# TivaC.net
KiCad netlist of a schematic drawn in Altium Designer
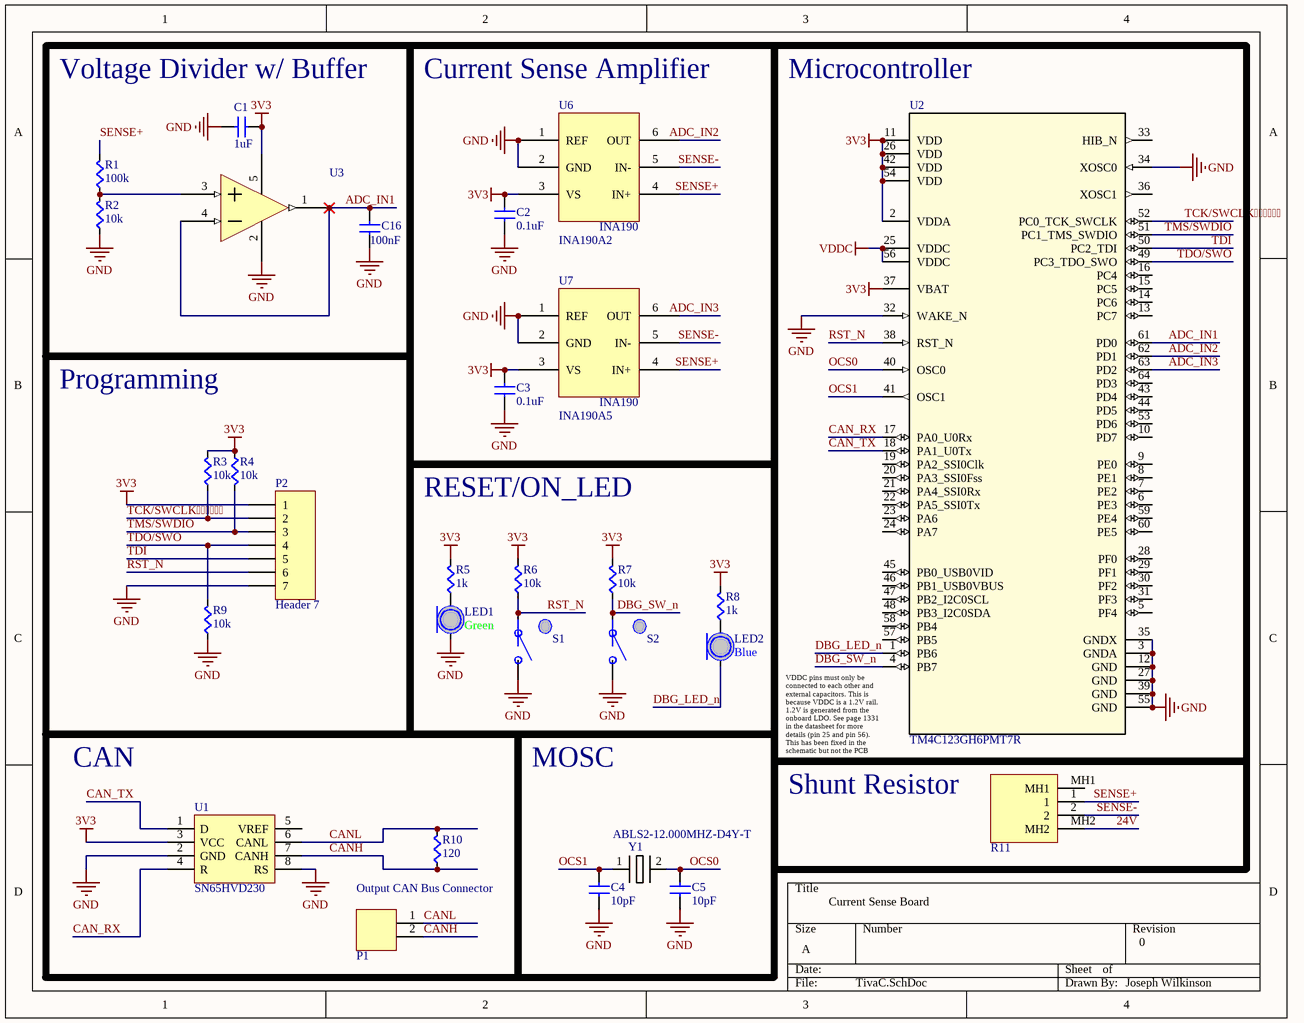
[diagram p0: TivaC.SchDoc]

(export (version "E")
  (design (tool "Eeschema 10.0.6"))
  (components
    (comp (ref "C1")
      (value "1uF")
      (footprint "CAPC0603")
      (fields (field (name "Comment") "Cap"))
      (libsource (lib "Passives") (part "Cap"))
    )
    (comp (ref "C2")
      (value "0.1uF")
      (footprint "CAPC0603")
      (fields (field (name "Comment") "Cap"))
      (libsource (lib "Passives") (part "Cap"))
    )
    (comp (ref "C3")
      (value "0.1uF")
      (footprint "CAPC0603")
      (fields (field (name "Comment") "Cap"))
      (libsource (lib "Passives") (part "Cap"))
    )
    (comp (ref "C4")
      (value "10pF")
      (footprint "CAPC0603")
      (fields (field (name "Comment") "Cap"))
      (libsource (lib "Passives") (part "Cap"))
    )
    (comp (ref "C5")
      (value "10pF")
      (footprint "CAPC0603")
      (fields (field (name "Comment") "Cap"))
      (libsource (lib "Passives") (part "Cap"))
    )
    (comp (ref "C16")
      (value "100nF")
      (footprint "CAPC0603")
      (fields (field (name "Comment") "Cap"))
      (libsource (lib "Passives") (part "Cap"))
    )
    (comp (ref "LED1")
      (value "LED")
      (footprint "LED0603")
      (fields (field (name "COLOR") "Green"))
      (libsource (lib "Semiconductors") (part "LED"))
    )
    (comp (ref "LED2")
      (value "LED")
      (footprint "LED0603")
      (fields (field (name "COLOR") "Blue"))
      (libsource (lib "Semiconductors") (part "LED"))
    )
    (comp (ref "P1")
      (value "2-pin Vert Sherlock")
      (footprint "MOLEX-HDR-1X2-SHERLOCK-VERT")
      (libsource (lib "Connectors") (part "MOLEX-HDR-1x2-SHERLOCK_VERT"))
    )
    (comp (ref "P2")
      (value "Header 7")
      (footprint "HDR1X7")
      (description "Header, 7-Pin")
      (fields (field (name "PUBLISHER") "Altium Limited"))
      (libsource (lib "Miscellaneous Connectors") (part "Header 7"))
    )
    (comp (ref "R1")
      (value "100k")
      (footprint "RES0603")
      (fields (field (name "Comment") "Res"))
      (libsource (lib "Passives") (part "Res"))
    )
    (comp (ref "R2")
      (value "10k")
      (footprint "RES0603")
      (fields (field (name "Comment") "Res"))
      (libsource (lib "Passives") (part "Res"))
    )
    (comp (ref "R3")
      (value "10k")
      (footprint "RES0603")
      (fields (field (name "Comment") "Res"))
      (libsource (lib "Passives") (part "Res"))
    )
    (comp (ref "R4")
      (value "10k")
      (footprint "RES0603")
      (fields (field (name "Comment") "Res"))
      (libsource (lib "Passives") (part "Res"))
    )
    (comp (ref "R5")
      (value "1k")
      (footprint "RES0603")
      (fields (field (name "Comment") "Res"))
      (libsource (lib "Passives") (part "Res"))
    )
    (comp (ref "R6")
      (value "10k")
      (footprint "RES0603")
      (fields (field (name "Comment") "Res"))
      (libsource (lib "Passives") (part "Res"))
    )
    (comp (ref "R7")
      (value "10k")
      (footprint "RES0603")
      (fields (field (name "Comment") "Res"))
      (libsource (lib "Passives") (part "Res"))
    )
    (comp (ref "R8")
      (value "1k")
      (footprint "RES0603")
      (fields (field (name "Comment") "Res"))
      (libsource (lib "Passives") (part "Res"))
    )
    (comp (ref "R9")
      (value "10k")
      (footprint "RES0603")
      (fields (field (name "Comment") "Res"))
      (libsource (lib "Passives") (part "Res"))
    )
    (comp (ref "R10")
      (value "120")
      (footprint "RES0603")
      (fields (field (name "Comment") "Res"))
      (libsource (lib "Passives") (part "Res"))
    )
    (comp (ref "R11")
      (value "SH6918F500BPEP")
      (footprint "SH6918F500BPEP")
      (description "Copper bus bar with shunt resistor integrated")
      (fields (field (name "MOUSER PART NUMBER") "588-SH6918F500BPEP"))
      (libsource (lib "Passives") (part "SH6918F500BPEP"))
    )
    (comp (ref "S1")
      (value "Button")
      (footprint "PTS645xxxxSMTR92")
      (description "SPST Button")
      (libsource (lib "Passives") (part "Button"))
    )
    (comp (ref "S2")
      (value "Button")
      (footprint "PTS645xxxxSMTR92")
      (description "SPST Button")
      (libsource (lib "Passives") (part "Button"))
    )
    (comp (ref "U1")
      (value "SN65HVD230")
      (footprint "SOIC-8pin")
      (description "3.3V CAN Bus Transceiver")
      (libsource (lib "ICs") (part "SN65HVD230"))
    )
    (comp (ref "U2")
      (value "TM4C123GH6PMT7R")
      (footprint "TM4C123GH6PMT7R_L")
      (description "Imported")
      (fields
        (field (name "PARTNUMBER") "TM4C123GH6PMTR")
        (field (name "ALTERNATE_PARTNUMBER") "TM4C123GH6PMT")
      )
      (libsource (lib "ICs") (part "TM4C123GH6PMT7R"))
    )
    (comp (ref "U3")
      (value "MCP6L01")
      (footprint "MCP6L01R")
      (description "Op Amp Rail-to-Rail 1Mhz")
      (libsource (lib "ICs") (part "MCP6L01"))
    )
    (comp (ref "U6")
      (value "INA190A2")
      (footprint "SC70 (DCK)")
      (libsource (lib "projectLib") (part "INA190"))
    )
    (comp (ref "U7")
      (value "INA190A5")
      (footprint "SC70 (DCK)")
      (libsource (lib "projectLib") (part "INA190"))
    )
    (comp (ref "Y1")
      (value "ABLS2-12.000MHZ-D4Y-T")
      (footprint "HC49/US")
      (description "12MHz ±30ppm Crystal 18pF 50 Ohm -40°C ~ 85°C Surface Mount HC49/US")
      (libsource (lib "ICs") (part "ABLS2-12.000MHZ-D4Y-T"))
    )
  )
  (nets
    (net (code "1") (name "/24V") (class "Default")
      (node (ref "R11") (pin "MH2") (pinfunction "MH2_MH2") (pintype "passive"))
    )
    (net (code "2") (name "/ADC_IN1") (class "Default")
      (node (ref "C16") (pin "1") (pinfunction "A_1") (pintype "passive"))
      (node (ref "U2") (pin "61") (pinfunction "PD0_61") (pintype "bidirectional"))
      (node (ref "U3") (pin "1") (pinfunction "VOUT_1") (pintype "output"))
      (node (ref "U3") (pin "4") (pinfunction "VIN-_4") (pintype "input"))
    )
    (net (code "3") (name "/ADC_IN2") (class "Default")
      (node (ref "U2") (pin "62") (pinfunction "PD1_62") (pintype "bidirectional"))
      (node (ref "U6") (pin "6") (pinfunction "OUT_6") (pintype "passive"))
    )
    (net (code "4") (name "/ADC_IN3") (class "Default")
      (node (ref "U2") (pin "63") (pinfunction "PD2_63") (pintype "bidirectional"))
      (node (ref "U7") (pin "6") (pinfunction "OUT_6") (pintype "passive"))
    )
    (net (code "5") (name "/CANH") (class "Default")
      (node (ref "P1") (pin "2") (pinfunction "2_2") (pintype "passive"))
      (node (ref "R10") (pin "2") (pinfunction "B_2") (pintype "passive"))
      (node (ref "U1") (pin "7") (pinfunction "CANH_7") (pintype "passive"))
    )
    (net (code "6") (name "/CANL") (class "Default")
      (node (ref "P1") (pin "1") (pinfunction "1_1") (pintype "passive"))
      (node (ref "R10") (pin "1") (pinfunction "A_1") (pintype "passive"))
      (node (ref "U1") (pin "6") (pinfunction "CANL_6") (pintype "passive"))
    )
    (net (code "7") (name "/CAN_RX") (class "Default")
      (node (ref "U1") (pin "4") (pinfunction "R_4") (pintype "passive"))
      (node (ref "U2") (pin "17") (pinfunction "PA0_U0Rx_17") (pintype "bidirectional"))
    )
    (net (code "8") (name "/CAN_TX") (class "Default")
      (node (ref "U1") (pin "1") (pinfunction "D_1") (pintype "passive"))
      (node (ref "U2") (pin "18") (pinfunction "PA1_U0Tx_18") (pintype "bidirectional"))
    )
    (net (code "9") (name "/DBG_LED_n") (class "Default")
      (node (ref "LED2") (pin "C") (pinfunction "C_C") (pintype "passive"))
      (node (ref "U2") (pin "1") (pinfunction "PB6_1") (pintype "bidirectional"))
    )
    (net (code "10") (name "/DBG_SW_n") (class "Default")
      (node (ref "R7") (pin "2") (pinfunction "B_2") (pintype "passive"))
      (node (ref "S2") (pin "A") (pinfunction "A_A") (pintype "passive"))
      (node (ref "U2") (pin "4") (pinfunction "PB7_4") (pintype "bidirectional"))
    )
    (net (code "11") (name "/OCS0") (class "Default")
      (node (ref "C5") (pin "1") (pinfunction "A_1") (pintype "passive"))
      (node (ref "U2") (pin "40") (pinfunction "OSC0_40") (pintype "input"))
      (node (ref "Y1") (pin "2") (pinfunction "2_2") (pintype "passive"))
    )
    (net (code "12") (name "/OCS1") (class "Default")
      (node (ref "C4") (pin "1") (pinfunction "A_1") (pintype "passive"))
      (node (ref "U2") (pin "41") (pinfunction "OSC1_41") (pintype "output"))
      (node (ref "Y1") (pin "1") (pinfunction "1_1") (pintype "passive"))
    )
    (net (code "13") (name "/RST_N") (class "Default")
      (node (ref "P2") (pin "6") (pinfunction "6_6") (pintype "passive"))
      (node (ref "R6") (pin "2") (pinfunction "B_2") (pintype "passive"))
      (node (ref "S1") (pin "A") (pinfunction "A_A") (pintype "passive"))
      (node (ref "U2") (pin "38") (pinfunction "RST_N_38") (pintype "input"))
    )
    (net (code "14") (name "/SENSE+") (class "Default")
      (node (ref "R1") (pin "1") (pinfunction "A_1") (pintype "passive"))
      (node (ref "R11") (pin "1") (pinfunction "1_1") (pintype "passive"))
      (node (ref "U6") (pin "4") (pinfunction "IN+_4") (pintype "passive"))
      (node (ref "U7") (pin "4") (pinfunction "IN+_4") (pintype "passive"))
    )
    (net (code "15") (name "/SENSE-") (class "Default")
      (node (ref "R11") (pin "2") (pinfunction "2_2") (pintype "passive"))
      (node (ref "U6") (pin "5") (pinfunction "IN-_5") (pintype "passive"))
      (node (ref "U7") (pin "5") (pinfunction "IN-_5") (pintype "passive"))
    )
    (net (code "16") (name "/TCK{slash}SWCLK") (class "Default")
      (node (ref "P2") (pin "2") (pinfunction "2_2") (pintype "passive"))
      (node (ref "R3") (pin "2") (pinfunction "B_2") (pintype "passive"))
      (node (ref "U2") (pin "52") (pinfunction "PC0_TCK_SWCLK_52") (pintype "bidirectional"))
    )
    (net (code "17") (name "/TDI") (class "Default")
      (node (ref "P2") (pin "5") (pinfunction "5_5") (pintype "passive"))
      (node (ref "U2") (pin "50") (pinfunction "PC2_TDI_50") (pintype "bidirectional"))
    )
    (net (code "18") (name "/TDO{slash}SWO") (class "Default")
      (node (ref "P2") (pin "4") (pinfunction "4_4") (pintype "passive"))
      (node (ref "R9") (pin "1") (pinfunction "A_1") (pintype "passive"))
      (node (ref "U2") (pin "49") (pinfunction "PC3_TDO_SWO_49") (pintype "bidirectional"))
    )
    (net (code "19") (name "/TMS{slash}SWDIO") (class "Default")
      (node (ref "P2") (pin "3") (pinfunction "3_3") (pintype "passive"))
      (node (ref "R4") (pin "1") (pinfunction "A_1") (pintype "passive"))
      (node (ref "U2") (pin "51") (pinfunction "PC1_TMS_SWDIO_51") (pintype "bidirectional"))
    )
    (net (code "20") (name "3V3") (class "Default")
      (node (ref "C1") (pin "2") (pinfunction "B_2") (pintype "passive"))
      (node (ref "C2") (pin "1") (pinfunction "A_1") (pintype "passive"))
      (node (ref "C3") (pin "1") (pinfunction "A_1") (pintype "passive"))
      (node (ref "P2") (pin "1") (pinfunction "1_1") (pintype "passive"))
      (node (ref "R3") (pin "1") (pinfunction "A_1") (pintype "passive"))
      (node (ref "R4") (pin "2") (pinfunction "B_2") (pintype "passive"))
      (node (ref "R5") (pin "1") (pinfunction "A_1") (pintype "passive"))
      (node (ref "R6") (pin "1") (pinfunction "A_1") (pintype "passive"))
      (node (ref "R7") (pin "1") (pinfunction "A_1") (pintype "passive"))
      (node (ref "R8") (pin "1") (pinfunction "A_1") (pintype "passive"))
      (node (ref "U1") (pin "3") (pinfunction "VCC_3") (pintype "passive"))
      (node (ref "U2") (pin "11") (pinfunction "VDD_11") (pintype "power_in"))
      (node (ref "U2") (pin "2") (pinfunction "VDDA_2") (pintype "power_in"))
      (node (ref "U2") (pin "26") (pinfunction "VDD_26") (pintype "power_in"))
      (node (ref "U2") (pin "37") (pinfunction "VBAT_37") (pintype "power_in"))
      (node (ref "U2") (pin "42") (pinfunction "VDD_42") (pintype "power_in"))
      (node (ref "U2") (pin "54") (pinfunction "VDD_54") (pintype "power_in"))
      (node (ref "U3") (pin "5") (pinfunction "VDD_5") (pintype "power_in"))
      (node (ref "U6") (pin "3") (pinfunction "VS_3") (pintype "passive"))
      (node (ref "U7") (pin "3") (pinfunction "VS_3") (pintype "passive"))
    )
    (net (code "21") (name "GND") (class "Default")
      (node (ref "C1") (pin "1") (pinfunction "A_1") (pintype "passive"))
      (node (ref "C16") (pin "2") (pinfunction "B_2") (pintype "passive"))
      (node (ref "C2") (pin "2") (pinfunction "B_2") (pintype "passive"))
      (node (ref "C3") (pin "2") (pinfunction "B_2") (pintype "passive"))
      (node (ref "C4") (pin "2") (pinfunction "B_2") (pintype "passive"))
      (node (ref "C5") (pin "2") (pinfunction "B_2") (pintype "passive"))
      (node (ref "LED1") (pin "C") (pinfunction "C_C") (pintype "passive"))
      (node (ref "P2") (pin "7") (pinfunction "7_7") (pintype "passive"))
      (node (ref "R2") (pin "2") (pinfunction "B_2") (pintype "passive"))
      (node (ref "R9") (pin "2") (pinfunction "B_2") (pintype "passive"))
      (node (ref "S1") (pin "B") (pinfunction "B_B") (pintype "passive"))
      (node (ref "S2") (pin "B") (pinfunction "B_B") (pintype "passive"))
      (node (ref "U1") (pin "2") (pinfunction "GND_2") (pintype "passive"))
      (node (ref "U1") (pin "8") (pinfunction "RS_8") (pintype "passive"))
      (node (ref "U2") (pin "12") (pinfunction "GND_12") (pintype "power_in"))
      (node (ref "U2") (pin "27") (pinfunction "GND_27") (pintype "power_in"))
      (node (ref "U2") (pin "3") (pinfunction "GNDA_3") (pintype "power_in"))
      (node (ref "U2") (pin "32") (pinfunction "WAKE_N_32") (pintype "input"))
      (node (ref "U2") (pin "34") (pinfunction "XOSC0_34") (pintype "input"))
      (node (ref "U2") (pin "35") (pinfunction "GNDX_35") (pintype "power_in"))
      (node (ref "U2") (pin "39") (pinfunction "GND_39") (pintype "power_in"))
      (node (ref "U2") (pin "55") (pinfunction "GND_55") (pintype "power_in"))
      (node (ref "U3") (pin "2") (pinfunction "VSS_2") (pintype "power_in"))
      (node (ref "U6") (pin "1") (pinfunction "REF_1") (pintype "passive"))
      (node (ref "U6") (pin "2") (pinfunction "GND_2") (pintype "passive"))
      (node (ref "U7") (pin "1") (pinfunction "REF_1") (pintype "passive"))
      (node (ref "U7") (pin "2") (pinfunction "GND_2") (pintype "passive"))
    )
    (net (code "22") (name "Net-(R1-B)") (class "Default")
      (node (ref "R1") (pin "2") (pinfunction "B_2") (pintype "passive"))
      (node (ref "R2") (pin "1") (pinfunction "A_1") (pintype "passive"))
      (node (ref "U3") (pin "3") (pinfunction "VIN+_3") (pintype "input"))
    )
    (net (code "23") (name "Net-(R5-B)") (class "Default")
      (node (ref "LED1") (pin "A") (pinfunction "A_A") (pintype "passive"))
      (node (ref "R5") (pin "2") (pinfunction "B_2") (pintype "passive"))
    )
    (net (code "24") (name "Net-(R8-B)") (class "Default")
      (node (ref "LED2") (pin "A") (pinfunction "A_A") (pintype "passive"))
      (node (ref "R8") (pin "2") (pinfunction "B_2") (pintype "passive"))
    )
    (net (code "25") (name "VDDC") (class "Default")
      (node (ref "U2") (pin "25") (pinfunction "VDDC_25") (pintype "power_in"))
      (node (ref "U2") (pin "56") (pinfunction "VDDC_56") (pintype "power_in"))
    )
    (net (code "26") (name "unconnected-(R11-PadMH1)") (class "Default")
      (node (ref "R11") (pin "MH1") (pinfunction "MH1_MH1") (pintype "passive"))
    )
    (net (code "27") (name "unconnected-(U1-VREF-Pad5)") (class "Default")
      (node (ref "U1") (pin "5") (pinfunction "VREF_5") (pintype "passive"))
    )
    (net (code "28") (name "unconnected-(U2-HIB_N-Pad33)") (class "Default")
      (node (ref "U2") (pin "33") (pinfunction "HIB_N_33") (pintype "output"))
    )
    (net (code "29") (name "unconnected-(U2-PA2_SSI0Clk-Pad19)") (class "Default")
      (node (ref "U2") (pin "19") (pinfunction "PA2_SSI0Clk_19") (pintype "bidirectional"))
    )
    (net (code "30") (name "unconnected-(U2-PA3_SSI0Fss-Pad20)") (class "Default")
      (node (ref "U2") (pin "20") (pinfunction "PA3_SSI0Fss_20") (pintype "bidirectional"))
    )
    (net (code "31") (name "unconnected-(U2-PA4_SSI0Rx-Pad21)") (class "Default")
      (node (ref "U2") (pin "21") (pinfunction "PA4_SSI0Rx_21") (pintype "bidirectional"))
    )
    (net (code "32") (name "unconnected-(U2-PA5_SSI0Tx-Pad22)") (class "Default")
      (node (ref "U2") (pin "22") (pinfunction "PA5_SSI0Tx_22") (pintype "bidirectional"))
    )
    (net (code "33") (name "unconnected-(U2-PA6-Pad23)") (class "Default")
      (node (ref "U2") (pin "23") (pinfunction "PA6_23") (pintype "bidirectional"))
    )
    (net (code "34") (name "unconnected-(U2-PA7-Pad24)") (class "Default")
      (node (ref "U2") (pin "24") (pinfunction "PA7_24") (pintype "bidirectional"))
    )
    (net (code "35") (name "unconnected-(U2-PB0_USB0VID-Pad45)") (class "Default")
      (node (ref "U2") (pin "45") (pinfunction "PB0_USB0VID_45") (pintype "bidirectional"))
    )
    (net (code "36") (name "unconnected-(U2-PB1_USB0VBUS-Pad46)") (class "Default")
      (node (ref "U2") (pin "46") (pinfunction "PB1_USB0VBUS_46") (pintype "bidirectional"))
    )
    (net (code "37") (name "unconnected-(U2-PB2_I2C0SCL-Pad47)") (class "Default")
      (node (ref "U2") (pin "47") (pinfunction "PB2_I2C0SCL_47") (pintype "bidirectional"))
    )
    (net (code "38") (name "unconnected-(U2-PB3_I2C0SDA-Pad48)") (class "Default")
      (node (ref "U2") (pin "48") (pinfunction "PB3_I2C0SDA_48") (pintype "bidirectional"))
    )
    (net (code "39") (name "unconnected-(U2-PB4-Pad58)") (class "Default")
      (node (ref "U2") (pin "58") (pinfunction "PB4_58") (pintype "bidirectional"))
    )
    (net (code "40") (name "unconnected-(U2-PB5-Pad57)") (class "Default")
      (node (ref "U2") (pin "57") (pinfunction "PB5_57") (pintype "bidirectional"))
    )
    (net (code "41") (name "unconnected-(U2-PC4-Pad16)") (class "Default")
      (node (ref "U2") (pin "16") (pinfunction "PC4_16") (pintype "bidirectional"))
    )
    (net (code "42") (name "unconnected-(U2-PC5-Pad15)") (class "Default")
      (node (ref "U2") (pin "15") (pinfunction "PC5_15") (pintype "bidirectional"))
    )
    (net (code "43") (name "unconnected-(U2-PC6-Pad14)") (class "Default")
      (node (ref "U2") (pin "14") (pinfunction "PC6_14") (pintype "bidirectional"))
    )
    (net (code "44") (name "unconnected-(U2-PC7-Pad13)") (class "Default")
      (node (ref "U2") (pin "13") (pinfunction "PC7_13") (pintype "bidirectional"))
    )
    (net (code "45") (name "unconnected-(U2-PD3-Pad64)") (class "Default")
      (node (ref "U2") (pin "64") (pinfunction "PD3_64") (pintype "bidirectional"))
    )
    (net (code "46") (name "unconnected-(U2-PD4-Pad43)") (class "Default")
      (node (ref "U2") (pin "43") (pinfunction "PD4_43") (pintype "bidirectional"))
    )
    (net (code "47") (name "unconnected-(U2-PD5-Pad44)") (class "Default")
      (node (ref "U2") (pin "44") (pinfunction "PD5_44") (pintype "bidirectional"))
    )
    (net (code "48") (name "unconnected-(U2-PD6-Pad53)") (class "Default")
      (node (ref "U2") (pin "53") (pinfunction "PD6_53") (pintype "bidirectional"))
    )
    (net (code "49") (name "unconnected-(U2-PD7-Pad10)") (class "Default")
      (node (ref "U2") (pin "10") (pinfunction "PD7_10") (pintype "bidirectional"))
    )
    (net (code "50") (name "unconnected-(U2-PE0-Pad9)") (class "Default")
      (node (ref "U2") (pin "9") (pinfunction "PE0_9") (pintype "bidirectional"))
    )
    (net (code "51") (name "unconnected-(U2-PE1-Pad8)") (class "Default")
      (node (ref "U2") (pin "8") (pinfunction "PE1_8") (pintype "bidirectional"))
    )
    (net (code "52") (name "unconnected-(U2-PE2-Pad7)") (class "Default")
      (node (ref "U2") (pin "7") (pinfunction "PE2_7") (pintype "bidirectional"))
    )
    (net (code "53") (name "unconnected-(U2-PE3-Pad6)") (class "Default")
      (node (ref "U2") (pin "6") (pinfunction "PE3_6") (pintype "bidirectional"))
    )
    (net (code "54") (name "unconnected-(U2-PE4-Pad59)") (class "Default")
      (node (ref "U2") (pin "59") (pinfunction "PE4_59") (pintype "bidirectional"))
    )
    (net (code "55") (name "unconnected-(U2-PE5-Pad60)") (class "Default")
      (node (ref "U2") (pin "60") (pinfunction "PE5_60") (pintype "bidirectional"))
    )
    (net (code "56") (name "unconnected-(U2-PF0-Pad28)") (class "Default")
      (node (ref "U2") (pin "28") (pinfunction "PF0_28") (pintype "bidirectional"))
    )
    (net (code "57") (name "unconnected-(U2-PF1-Pad29)") (class "Default")
      (node (ref "U2") (pin "29") (pinfunction "PF1_29") (pintype "bidirectional"))
    )
    (net (code "58") (name "unconnected-(U2-PF2-Pad30)") (class "Default")
      (node (ref "U2") (pin "30") (pinfunction "PF2_30") (pintype "bidirectional"))
    )
    (net (code "59") (name "unconnected-(U2-PF3-Pad31)") (class "Default")
      (node (ref "U2") (pin "31") (pinfunction "PF3_31") (pintype "bidirectional"))
    )
    (net (code "60") (name "unconnected-(U2-PF4-Pad5)") (class "Default")
      (node (ref "U2") (pin "5") (pinfunction "PF4_5") (pintype "bidirectional"))
    )
    (net (code "61") (name "unconnected-(U2-XOSC1-Pad36)") (class "Default")
      (node (ref "U2") (pin "36") (pinfunction "XOSC1_36") (pintype "output"))
    )
  )
)
